# KM_BD01.net
KiCad netlist of a schematic drawn in Altium Designer
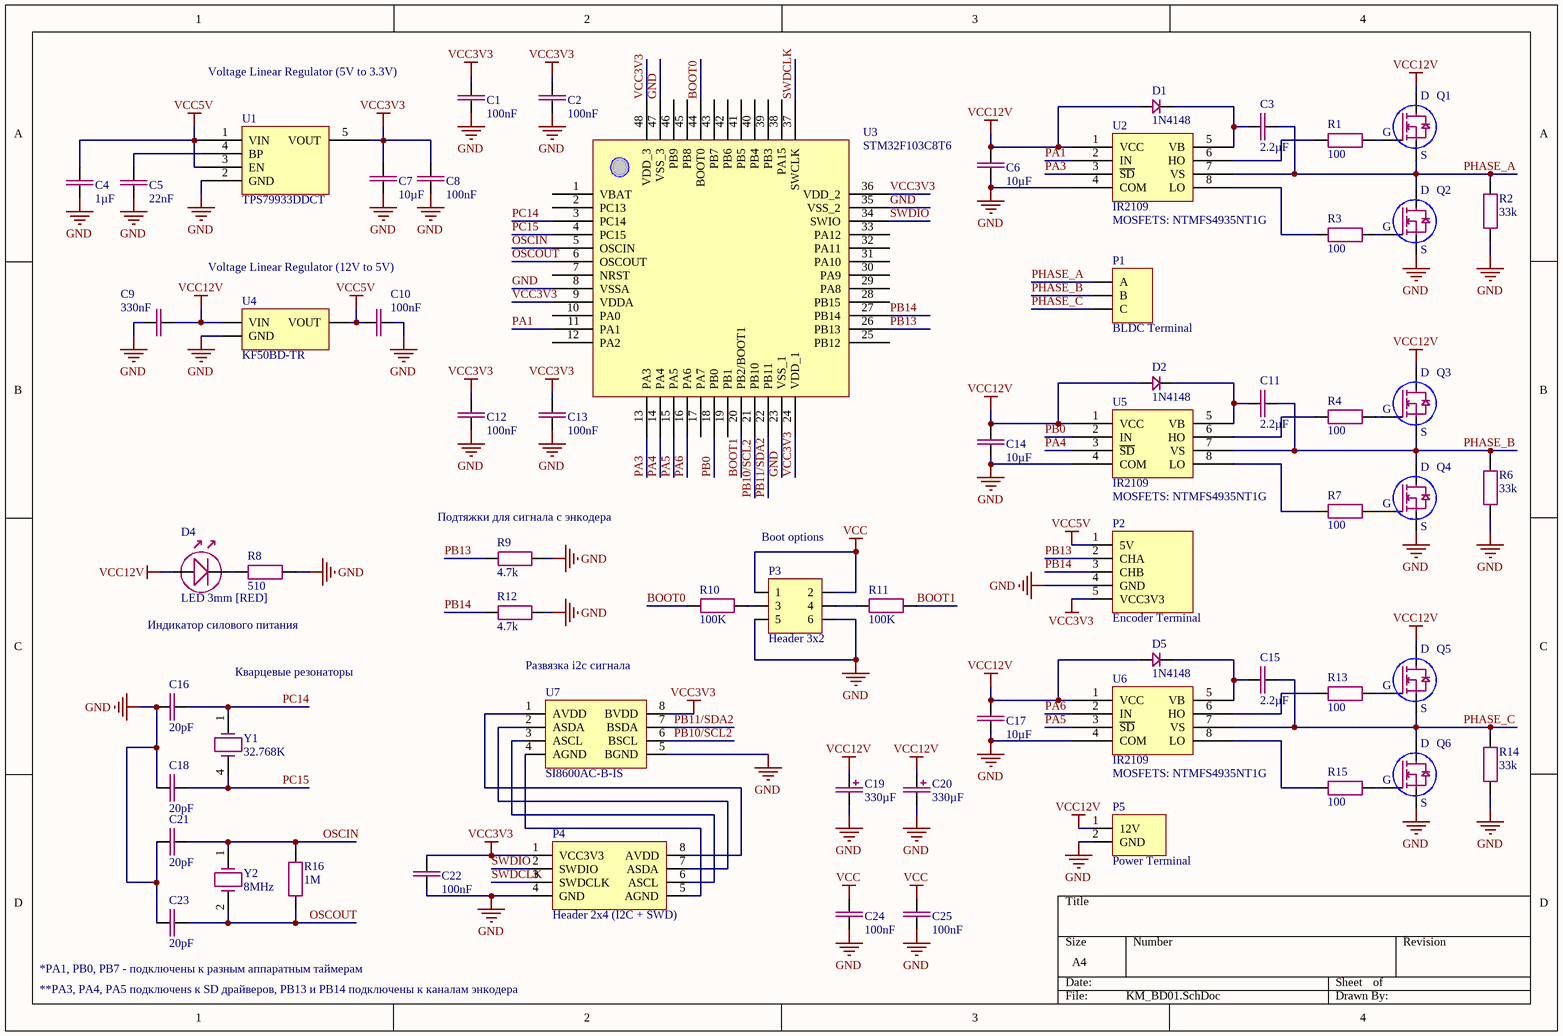
[diagram p0: KM_BD01.SchDoc]

(export (version "E")
  (design (tool "Eeschema 10.0.6"))
  (components
    (comp (ref "C1")
      (value "100nF")
      (footprint "KM_BD01:SMD 1206 CAP")
      (description "Capacitor 100nF [104]")
      (libsource (lib "KM_BD01") (part "100nF"))
    )
    (comp (ref "C2")
      (value "100nF")
      (footprint "KM_BD01:SMD 1206 CAP")
      (description "Capacitor 100nF [104]")
      (libsource (lib "KM_BD01") (part "100nF"))
    )
    (comp (ref "C3")
      (value "2.2µF")
      (footprint "KM_BD01:SMD 1206 CAP")
      (description "Capacitor 2.2µF [205]")
      (libsource (lib "KM_BD01") (part "2.2µF"))
    )
    (comp (ref "C4")
      (value "1µF")
      (footprint "KM_BD01:SMD 1206 CAP")
      (description "Capacitor 1µF [105]")
      (libsource (lib "KM_BD01") (part "1µF"))
    )
    (comp (ref "C5")
      (value "22nF")
      (footprint "KM_BD01:SMD 1206 CAP")
      (description "Capacitor 22nF [223]")
      (libsource (lib "KM_BD01") (part "22nF"))
    )
    (comp (ref "C6")
      (value "10µF")
      (footprint "KM_BD01:SMD 1206 CAP")
      (description "Capacitor 10µF [106]")
      (libsource (lib "KM_BD01") (part "10µF"))
    )
    (comp (ref "C7")
      (value "10µF")
      (footprint "KM_BD01:SMD 1206 CAP")
      (description "Capacitor 10µF [106]")
      (libsource (lib "KM_BD01") (part "10µF"))
    )
    (comp (ref "C8")
      (value "100nF")
      (footprint "KM_BD01:SMD 1206 CAP")
      (description "Capacitor 100nF [104]")
      (libsource (lib "KM_BD01") (part "100nF"))
    )
    (comp (ref "C9")
      (value "330nF")
      (footprint "KM_BD01:SMD 1206 CAP")
      (description "Capacitor 330nF [334]")
      (libsource (lib "KM_BD01") (part "330nF"))
    )
    (comp (ref "C10")
      (value "100nF")
      (footprint "KM_BD01:SMD 1206 CAP")
      (description "Capacitor 100nF [104]")
      (libsource (lib "KM_BD01") (part "100nF"))
    )
    (comp (ref "C11")
      (value "2.2µF")
      (footprint "KM_BD01:SMD 1206 CAP")
      (description "Capacitor 2.2µF [205]")
      (libsource (lib "KM_BD01") (part "2.2µF"))
    )
    (comp (ref "C12")
      (value "100nF")
      (footprint "KM_BD01:SMD 1206 CAP")
      (description "Capacitor 100nF [104]")
      (libsource (lib "KM_BD01") (part "100nF"))
    )
    (comp (ref "C13")
      (value "100nF")
      (footprint "KM_BD01:SMD 1206 CAP")
      (description "Capacitor 100nF [104]")
      (libsource (lib "KM_BD01") (part "100nF"))
    )
    (comp (ref "C14")
      (value "10µF")
      (footprint "KM_BD01:SMD 1206 CAP")
      (description "Capacitor 10µF [106]")
      (libsource (lib "KM_BD01") (part "10µF"))
    )
    (comp (ref "C15")
      (value "2.2µF")
      (footprint "KM_BD01:SMD 1206 CAP")
      (description "Capacitor 2.2µF [205]")
      (libsource (lib "KM_BD01") (part "2.2µF"))
    )
    (comp (ref "C16")
      (value "20pF")
      (footprint "KM_BD01:SMD 1206 CAP")
      (description "Capacitor 20pF")
      (libsource (lib "KM_BD01") (part "20pF"))
    )
    (comp (ref "C17")
      (value "10µF")
      (footprint "KM_BD01:SMD 1206 CAP")
      (description "Capacitor 10µF [106]")
      (libsource (lib "KM_BD01") (part "10µF"))
    )
    (comp (ref "C18")
      (value "20pF")
      (footprint "KM_BD01:SMD 1206 CAP")
      (description "Capacitor 20pF")
      (libsource (lib "KM_BD01") (part "20pF"))
    )
    (comp (ref "C19")
      (value "330µF")
      (footprint "KM_BD01:THD 6.3x11 CAP")
      (description "Capacitor 330µF [336]")
      (libsource (lib "KM_BD01") (part "330µF"))
    )
    (comp (ref "C20")
      (value "330µF")
      (footprint "KM_BD01:THD 6.3x11 CAP")
      (description "Capacitor 330µF [336]")
      (libsource (lib "KM_BD01") (part "330µF"))
    )
    (comp (ref "C21")
      (value "20pF")
      (footprint "KM_BD01:SMD 1206 CAP")
      (description "Capacitor 20pF")
      (libsource (lib "KM_BD01") (part "20pF"))
    )
    (comp (ref "C22")
      (value "100nF")
      (footprint "KM_BD01:SMD 1206 CAP")
      (description "Capacitor 100nF [104]")
      (libsource (lib "KM_BD01") (part "100nF"))
    )
    (comp (ref "C23")
      (value "20pF")
      (footprint "KM_BD01:SMD 1206 CAP")
      (description "Capacitor 20pF")
      (libsource (lib "KM_BD01") (part "20pF"))
    )
    (comp (ref "C24")
      (value "100nF")
      (footprint "KM_BD01:SMD 1206 CAP")
      (description "Capacitor 100nF [104]")
      (libsource (lib "KM_BD01") (part "100nF"))
    )
    (comp (ref "C25")
      (value "100nF")
      (footprint "KM_BD01:SMD 1206 CAP")
      (description "Capacitor 100nF [104]")
      (libsource (lib "KM_BD01") (part "100nF"))
    )
    (comp (ref "D1")
      (value "1N4148")
      (footprint "KM_BD01:DO-35")
      (description "Fast diode")
      (libsource (lib "KM_BD01") (part "1N4148"))
    )
    (comp (ref "D2")
      (value "1N4148")
      (footprint "KM_BD01:DO-35")
      (description "Fast diode")
      (libsource (lib "KM_BD01") (part "1N4148"))
    )
    (comp (ref "D4")
      (value "LED 3mm [RED]")
      (footprint "KM_BD01:LED 3mm RED")
      (libsource (lib "KM_BD01") (part "LED 3mm [RED]"))
    )
    (comp (ref "D5")
      (value "1N4148")
      (footprint "KM_BD01:DO-35")
      (description "Fast diode")
      (libsource (lib "KM_BD01") (part "1N4148"))
    )
    (comp (ref "P1")
      (value "BLDC Terminal")
      (footprint "KM_BD01:Universal 3-Phase Terminal")
      (description "3-pad terminal")
      (libsource (lib "KM_BD01") (part "BLDC Terminal"))
    )
    (comp (ref "P2")
      (value "Encoder Terminal")
      (footprint "KM_BD01:PLS_5")
      (description "5-pin PLS terminal")
      (libsource (lib "KM_BD01") (part "Encoder Terminal"))
    )
    (comp (ref "P3")
      (value "Header 3x2")
      (footprint "KM_BD01:PLS_3x2 (Without legs)")
      (description "6-pin PLS terminal")
      (libsource (lib "KM_BD01") (part "Header 3x2"))
    )
    (comp (ref "P4")
      (value "Header 2x4 (I2C + SWD)")
      (footprint "KM_BD01:PLS_4x2")
      (description "8-pin PLS terminal")
      (libsource (lib "KM_BD01") (part "Header 2x4 (I2C + SWD)"))
    )
    (comp (ref "P5")
      (value "Power Terminal")
      (footprint "KM_BD01:Universal Power Terminal")
      (description "12V 2-pad terminal")
      (libsource (lib "KM_BD01") (part "Power Terminal"))
    )
    (comp (ref "Q1")
      (value "NTMFS4935NT1G")
      (footprint "KM_BD01:SO-8FL")
      (description "Mosfet [OptiMOS]")
      (libsource (lib "KM_BD01") (part "NTMFS4935NT1G"))
    )
    (comp (ref "Q2")
      (value "NTMFS4935NT1G")
      (footprint "KM_BD01:SO-8FL")
      (description "Mosfet [OptiMOS]")
      (libsource (lib "KM_BD01") (part "NTMFS4935NT1G"))
    )
    (comp (ref "Q3")
      (value "NTMFS4935NT1G")
      (footprint "KM_BD01:SO-8FL")
      (description "Mosfet [OptiMOS]")
      (libsource (lib "KM_BD01") (part "NTMFS4935NT1G"))
    )
    (comp (ref "Q4")
      (value "NTMFS4935NT1G")
      (footprint "KM_BD01:SO-8FL")
      (description "Mosfet [OptiMOS]")
      (libsource (lib "KM_BD01") (part "NTMFS4935NT1G"))
    )
    (comp (ref "Q5")
      (value "NTMFS4935NT1G")
      (footprint "KM_BD01:SO-8FL")
      (description "Mosfet [OptiMOS]")
      (libsource (lib "KM_BD01") (part "NTMFS4935NT1G"))
    )
    (comp (ref "Q6")
      (value "NTMFS4935NT1G")
      (footprint "KM_BD01:SO-8FL")
      (description "Mosfet [OptiMOS]")
      (libsource (lib "KM_BD01") (part "NTMFS4935NT1G"))
    )
    (comp (ref "R1")
      (value "100")
      (footprint "KM_BD01:SMD 1206 RES")
      (description "Resistor")
      (libsource (lib "KM_BD01") (part "100"))
    )
    (comp (ref "R2")
      (value "33k")
      (footprint "KM_BD01:SMD 1206 RES")
      (description "Resistor")
      (libsource (lib "KM_BD01") (part "33k"))
    )
    (comp (ref "R3")
      (value "100")
      (footprint "KM_BD01:SMD 1206 RES")
      (description "Resistor")
      (libsource (lib "KM_BD01") (part "100"))
    )
    (comp (ref "R4")
      (value "100")
      (footprint "KM_BD01:SMD 1206 RES")
      (description "Resistor")
      (libsource (lib "KM_BD01") (part "100"))
    )
    (comp (ref "R6")
      (value "33k")
      (footprint "KM_BD01:SMD 1206 RES")
      (description "Resistor")
      (libsource (lib "KM_BD01") (part "33k"))
    )
    (comp (ref "R7")
      (value "100")
      (footprint "KM_BD01:SMD 1206 RES")
      (description "Resistor")
      (libsource (lib "KM_BD01") (part "100"))
    )
    (comp (ref "R8")
      (value "510")
      (footprint "KM_BD01:SMD 1206 RES")
      (description "Resistor")
      (libsource (lib "KM_BD01") (part "510"))
    )
    (comp (ref "R9")
      (value "4.7k")
      (footprint "KM_BD01:SMD 1206 RES")
      (description "Resistor")
      (libsource (lib "KM_BD01") (part "4.7k"))
    )
    (comp (ref "R10")
      (value "100K")
      (footprint "KM_BD01:SMD 1206 RES")
      (description "Resistor")
      (libsource (lib "KM_BD01") (part "100K"))
    )
    (comp (ref "R11")
      (value "100K")
      (footprint "KM_BD01:SMD 1206 RES")
      (description "Resistor")
      (libsource (lib "KM_BD01") (part "100K"))
    )
    (comp (ref "R12")
      (value "4.7k")
      (footprint "KM_BD01:SMD 1206 RES")
      (description "Resistor")
      (libsource (lib "KM_BD01") (part "4.7k"))
    )
    (comp (ref "R13")
      (value "100")
      (footprint "KM_BD01:SMD 1206 RES")
      (description "Resistor")
      (libsource (lib "KM_BD01") (part "100"))
    )
    (comp (ref "R14")
      (value "33k")
      (footprint "KM_BD01:SMD 1206 RES")
      (description "Resistor")
      (libsource (lib "KM_BD01") (part "33k"))
    )
    (comp (ref "R15")
      (value "100")
      (footprint "KM_BD01:SMD 1206 RES")
      (description "Resistor")
      (libsource (lib "KM_BD01") (part "100"))
    )
    (comp (ref "R16")
      (value "1M")
      (footprint "KM_BD01:SMD 1206 RES")
      (description "Resistor")
      (libsource (lib "KM_BD01") (part "1M"))
    )
    (comp (ref "U1")
      (value "TPS79933DDCT")
      (footprint "KM_BD01:SOT95P245X110-5N")
      (description "Linear Voltage Regulator (3.3V)")
      (libsource (lib "KM_BD01") (part "TPS79933DDCT"))
    )
    (comp (ref "U2")
      (value "IR2109")
      (footprint "KM_BD01:SOIC-8")
      (description "Fast Half-Bridge Driver")
      (libsource (lib "KM_BD01") (part "IR2109"))
    )
    (comp (ref "U3")
      (value "STM32F103C8T6")
      (footprint "KM_BD01:TQFP-48")
      (description "Microcontroller")
      (libsource (lib "KM_BD01") (part "STM32F103C8T6"))
    )
    (comp (ref "U4")
      (value "KF50BD-TR")
      (footprint "KM_BD01:SOIC-8 (KF50BD-TR)")
      (description "Linear Voltage Regulator (5V)")
      (libsource (lib "KM_BD01") (part "KF50BD-TR"))
    )
    (comp (ref "U5")
      (value "IR2109")
      (footprint "KM_BD01:SOIC-8")
      (description "Fast Half-Bridge Driver")
      (libsource (lib "KM_BD01") (part "IR2109"))
    )
    (comp (ref "U6")
      (value "IR2109")
      (footprint "KM_BD01:SOIC-8")
      (description "Fast Half-Bridge Driver")
      (libsource (lib "KM_BD01") (part "IR2109"))
    )
    (comp (ref "U7")
      (value "SI8600AC-B-IS")
      (footprint "KM_BD01:SOIC-8")
      (description "Bidirectional I2C isolator")
      (libsource (lib "KM_BD01") (part "SI8600AC-B-IS"))
    )
    (comp (ref "Y1")
      (value "32.768K")
      (footprint "KM_BD01:SMD 0803-8P4")
      (description "Oscillator")
      (libsource (lib "KM_BD01") (part "32.768K"))
    )
    (comp (ref "Y2")
      (value "8MHz")
      (footprint "KM_BD01:HC-49SM")
      (description "Oscillator")
      (libsource (lib "KM_BD01") (part "8MHz"))
    )
  )
  (nets
    (net (code "1") (name "/BOOT0") (class "Default")
      (node (ref "R10") (pin "1") (pinfunction "1_1") (pintype "passive"))
      (node (ref "U3") (pin "44") (pinfunction "BOOT0_44") (pintype "passive"))
    )
    (net (code "2") (name "/BOOT1") (class "Default")
      (node (ref "R11") (pin "2") (pinfunction "2_2") (pintype "passive"))
      (node (ref "U3") (pin "20") (pinfunction "PB2/BOOT1_20") (pintype "passive"))
    )
    (net (code "3") (name "/OSCIN") (class "Default")
      (node (ref "C21") (pin "2") (pinfunction "2_2") (pintype "passive"))
      (node (ref "R16") (pin "2") (pinfunction "2_2") (pintype "passive"))
      (node (ref "U3") (pin "5") (pinfunction "OSCIN_5") (pintype "passive"))
      (node (ref "Y2") (pin "1") (pinfunction "1_1") (pintype "passive"))
    )
    (net (code "4") (name "/OSCOUT") (class "Default")
      (node (ref "C23") (pin "2") (pinfunction "2_2") (pintype "passive"))
      (node (ref "R16") (pin "1") (pinfunction "1_1") (pintype "passive"))
      (node (ref "U3") (pin "6") (pinfunction "OSCOUT_6") (pintype "passive"))
      (node (ref "Y2") (pin "2") (pinfunction "2_2") (pintype "passive"))
    )
    (net (code "5") (name "/PA1") (class "Default")
      (node (ref "U2") (pin "2") (pinfunction "IN_2") (pintype "passive"))
      (node (ref "U3") (pin "11") (pinfunction "PA1_11") (pintype "passive"))
    )
    (net (code "6") (name "/PA3") (class "Default")
      (node (ref "U2") (pin "3") (pinfunction "~{SD}_3") (pintype "passive"))
      (node (ref "U3") (pin "13") (pinfunction "PA3_13") (pintype "passive"))
    )
    (net (code "7") (name "/PA4") (class "Default")
      (node (ref "U3") (pin "14") (pinfunction "PA4_14") (pintype "passive"))
      (node (ref "U5") (pin "3") (pinfunction "~{SD}_3") (pintype "passive"))
    )
    (net (code "8") (name "/PA5") (class "Default")
      (node (ref "U3") (pin "15") (pinfunction "PA5_15") (pintype "passive"))
      (node (ref "U6") (pin "3") (pinfunction "~{SD}_3") (pintype "passive"))
    )
    (net (code "9") (name "/PA6") (class "Default")
      (node (ref "U3") (pin "16") (pinfunction "PA6_16") (pintype "passive"))
      (node (ref "U6") (pin "2") (pinfunction "IN_2") (pintype "passive"))
    )
    (net (code "10") (name "/PB0") (class "Default")
      (node (ref "U3") (pin "18") (pinfunction "PB0_18") (pintype "passive"))
      (node (ref "U5") (pin "2") (pinfunction "IN_2") (pintype "passive"))
    )
    (net (code "11") (name "/PB10{slash}SCL2") (class "Default")
      (node (ref "U3") (pin "21") (pinfunction "PB10_21") (pintype "passive"))
      (node (ref "U7") (pin "6") (pinfunction "BSCL_6") (pintype "passive"))
    )
    (net (code "12") (name "/PB11{slash}SDA2") (class "Default")
      (node (ref "U3") (pin "22") (pinfunction "PB11_22") (pintype "passive"))
      (node (ref "U7") (pin "7") (pinfunction "BSDA_7") (pintype "passive"))
    )
    (net (code "13") (name "/PB13") (class "Default")
      (node (ref "P2") (pin "2") (pinfunction "CHA_2") (pintype "passive"))
      (node (ref "R9") (pin "2") (pinfunction "2_2") (pintype "passive"))
      (node (ref "U3") (pin "26") (pinfunction "PB13_26") (pintype "passive"))
    )
    (net (code "14") (name "/PB14") (class "Default")
      (node (ref "P2") (pin "3") (pinfunction "CHB_3") (pintype "passive"))
      (node (ref "R12") (pin "2") (pinfunction "2_2") (pintype "passive"))
      (node (ref "U3") (pin "27") (pinfunction "PB14_27") (pintype "passive"))
    )
    (net (code "15") (name "/PC14") (class "Default")
      (node (ref "C16") (pin "2") (pinfunction "2_2") (pintype "passive"))
      (node (ref "U3") (pin "3") (pinfunction "PC14_3") (pintype "passive"))
      (node (ref "Y1") (pin "1") (pinfunction "1_1") (pintype "passive"))
    )
    (net (code "16") (name "/PC15") (class "Default")
      (node (ref "C18") (pin "2") (pinfunction "2_2") (pintype "passive"))
      (node (ref "U3") (pin "4") (pinfunction "PC15_4") (pintype "passive"))
      (node (ref "Y1") (pin "4") (pinfunction "4_4") (pintype "passive"))
    )
    (net (code "17") (name "/PHASE_A") (class "Default")
      (node (ref "C3") (pin "2") (pinfunction "2_2") (pintype "passive"))
      (node (ref "P1") (pin "1") (pinfunction "A_1") (pintype "passive"))
      (node (ref "Q1") (pin "2") (pinfunction "S_2") (pintype "passive"))
      (node (ref "Q2") (pin "3") (pinfunction "D_3") (pintype "passive"))
      (node (ref "R2") (pin "2") (pinfunction "2_2") (pintype "passive"))
      (node (ref "U2") (pin "7") (pinfunction "VS_7") (pintype "passive"))
    )
    (net (code "18") (name "/PHASE_B") (class "Default")
      (node (ref "C11") (pin "2") (pinfunction "2_2") (pintype "passive"))
      (node (ref "P1") (pin "2") (pinfunction "B_2") (pintype "passive"))
      (node (ref "Q3") (pin "2") (pinfunction "S_2") (pintype "passive"))
      (node (ref "Q4") (pin "3") (pinfunction "D_3") (pintype "passive"))
      (node (ref "R6") (pin "2") (pinfunction "2_2") (pintype "passive"))
      (node (ref "U5") (pin "7") (pinfunction "VS_7") (pintype "passive"))
    )
    (net (code "19") (name "/PHASE_C") (class "Default")
      (node (ref "C15") (pin "2") (pinfunction "2_2") (pintype "passive"))
      (node (ref "P1") (pin "3") (pinfunction "C_3") (pintype "passive"))
      (node (ref "Q5") (pin "2") (pinfunction "S_2") (pintype "passive"))
      (node (ref "Q6") (pin "3") (pinfunction "D_3") (pintype "passive"))
      (node (ref "R14") (pin "2") (pinfunction "2_2") (pintype "passive"))
      (node (ref "U6") (pin "7") (pinfunction "VS_7") (pintype "passive"))
    )
    (net (code "20") (name "/SWDCLK") (class "Default")
      (node (ref "P4") (pin "3") (pinfunction "SWDCLK_3") (pintype "passive"))
      (node (ref "U3") (pin "37") (pinfunction "SWCLK_37") (pintype "passive"))
    )
    (net (code "21") (name "/SWDIO") (class "Default")
      (node (ref "P4") (pin "2") (pinfunction "SWDIO_2") (pintype "passive"))
      (node (ref "U3") (pin "34") (pinfunction "SWIO_34") (pintype "passive"))
    )
    (net (code "22") (name "GND") (class "Default")
      (node (ref "C1") (pin "1") (pinfunction "1_1") (pintype "passive"))
      (node (ref "C10") (pin "2") (pinfunction "2_2") (pintype "passive"))
      (node (ref "C12") (pin "1") (pinfunction "1_1") (pintype "passive"))
      (node (ref "C13") (pin "1") (pinfunction "1_1") (pintype "passive"))
      (node (ref "C14") (pin "1") (pinfunction "1_1") (pintype "passive"))
      (node (ref "C16") (pin "1") (pinfunction "1_1") (pintype "passive"))
      (node (ref "C17") (pin "1") (pinfunction "1_1") (pintype "passive"))
      (node (ref "C18") (pin "1") (pinfunction "1_1") (pintype "passive"))
      (node (ref "C19") (pin "2") (pinfunction "2_2") (pintype "passive"))
      (node (ref "C2") (pin "1") (pinfunction "1_1") (pintype "passive"))
      (node (ref "C20") (pin "2") (pinfunction "2_2") (pintype "passive"))
      (node (ref "C21") (pin "1") (pinfunction "1_1") (pintype "passive"))
      (node (ref "C22") (pin "1") (pinfunction "1_1") (pintype "passive"))
      (node (ref "C23") (pin "1") (pinfunction "1_1") (pintype "passive"))
      (node (ref "C24") (pin "1") (pinfunction "1_1") (pintype "passive"))
      (node (ref "C25") (pin "1") (pinfunction "1_1") (pintype "passive"))
      (node (ref "C4") (pin "1") (pinfunction "1_1") (pintype "passive"))
      (node (ref "C5") (pin "1") (pinfunction "1_1") (pintype "passive"))
      (node (ref "C6") (pin "1") (pinfunction "1_1") (pintype "passive"))
      (node (ref "C7") (pin "1") (pinfunction "1_1") (pintype "passive"))
      (node (ref "C8") (pin "1") (pinfunction "1_1") (pintype "passive"))
      (node (ref "C9") (pin "1") (pinfunction "1_1") (pintype "passive"))
      (node (ref "P2") (pin "4") (pinfunction "GND_4") (pintype "passive"))
      (node (ref "P3") (pin "5") (pinfunction "5_5") (pintype "passive"))
      (node (ref "P3") (pin "6") (pinfunction "6_6") (pintype "passive"))
      (node (ref "P4") (pin "4") (pinfunction "GND_4") (pintype "passive"))
      (node (ref "P5") (pin "2") (pinfunction "GND_2") (pintype "passive"))
      (node (ref "Q2") (pin "2") (pinfunction "S_2") (pintype "passive"))
      (node (ref "Q4") (pin "2") (pinfunction "S_2") (pintype "passive"))
      (node (ref "Q6") (pin "2") (pinfunction "S_2") (pintype "passive"))
      (node (ref "R12") (pin "1") (pinfunction "1_1") (pintype "passive"))
      (node (ref "R14") (pin "1") (pinfunction "1_1") (pintype "passive"))
      (node (ref "R2") (pin "1") (pinfunction "1_1") (pintype "passive"))
      (node (ref "R6") (pin "1") (pinfunction "1_1") (pintype "passive"))
      (node (ref "R8") (pin "2") (pinfunction "2_2") (pintype "passive"))
      (node (ref "R9") (pin "1") (pinfunction "1_1") (pintype "passive"))
      (node (ref "U1") (pin "2") (pinfunction "GND_2") (pintype "passive"))
      (node (ref "U2") (pin "4") (pinfunction "COM_4") (pintype "passive"))
      (node (ref "U3") (pin "23") (pinfunction "VSS_1_23") (pintype "passive"))
      (node (ref "U3") (pin "35") (pinfunction "VSS_2_35") (pintype "passive"))
      (node (ref "U3") (pin "47") (pinfunction "VSS_3_47") (pintype "passive"))
      (node (ref "U3") (pin "8") (pinfunction "VSSA_8") (pintype "passive"))
      (node (ref "U4") (pin "2") (pinfunction "GND_2") (pintype "passive"))
      (node (ref "U5") (pin "4") (pinfunction "COM_4") (pintype "passive"))
      (node (ref "U6") (pin "4") (pinfunction "COM_4") (pintype "passive"))
      (node (ref "U7") (pin "5") (pinfunction "BGND_5") (pintype "passive"))
    )
    (net (code "23") (name "Net-(D4-Pad2)") (class "Default")
      (node (ref "D4") (pin "2") (pinfunction "2_2") (pintype "passive"))
      (node (ref "R8") (pin "1") (pinfunction "1_1") (pintype "passive"))
    )
    (net (code "24") (name "Net-(P3-Pad3)") (class "Default")
      (node (ref "P3") (pin "3") (pinfunction "3_3") (pintype "passive"))
      (node (ref "R10") (pin "2") (pinfunction "2_2") (pintype "passive"))
    )
    (net (code "25") (name "Net-(P3-Pad4)") (class "Default")
      (node (ref "P3") (pin "4") (pinfunction "4_4") (pintype "passive"))
      (node (ref "R11") (pin "1") (pinfunction "1_1") (pintype "passive"))
    )
    (net (code "26") (name "Net-(P4-AGND)") (class "Default")
      (node (ref "P4") (pin "5") (pinfunction "AGND_5") (pintype "passive"))
      (node (ref "U7") (pin "4") (pinfunction "AGND_4") (pintype "passive"))
    )
    (net (code "27") (name "Net-(P4-ASCL)") (class "Default")
      (node (ref "P4") (pin "6") (pinfunction "ASCL_6") (pintype "passive"))
      (node (ref "U7") (pin "3") (pinfunction "ASCL_3") (pintype "passive"))
    )
    (net (code "28") (name "Net-(P4-ASDA)") (class "Default")
      (node (ref "P4") (pin "7") (pinfunction "ASDA_7") (pintype "passive"))
      (node (ref "U7") (pin "2") (pinfunction "ASDA_2") (pintype "passive"))
    )
    (net (code "29") (name "Net-(P4-AVDD)") (class "Default")
      (node (ref "P4") (pin "8") (pinfunction "AVDD_8") (pintype "passive"))
      (node (ref "U7") (pin "1") (pinfunction "AVDD_1") (pintype "passive"))
    )
    (net (code "30") (name "Net-(Q1-G)") (class "Default")
      (node (ref "Q1") (pin "1") (pinfunction "G_1") (pintype "passive"))
      (node (ref "R1") (pin "2") (pinfunction "2_2") (pintype "passive"))
    )
    (net (code "31") (name "Net-(Q2-G)") (class "Default")
      (node (ref "Q2") (pin "1") (pinfunction "G_1") (pintype "passive"))
      (node (ref "R3") (pin "2") (pinfunction "2_2") (pintype "passive"))
    )
    (net (code "32") (name "Net-(Q3-G)") (class "Default")
      (node (ref "Q3") (pin "1") (pinfunction "G_1") (pintype "passive"))
      (node (ref "R4") (pin "2") (pinfunction "2_2") (pintype "passive"))
    )
    (net (code "33") (name "Net-(Q4-G)") (class "Default")
      (node (ref "Q4") (pin "1") (pinfunction "G_1") (pintype "passive"))
      (node (ref "R7") (pin "2") (pinfunction "2_2") (pintype "passive"))
    )
    (net (code "34") (name "Net-(Q5-G)") (class "Default")
      (node (ref "Q5") (pin "1") (pinfunction "G_1") (pintype "passive"))
      (node (ref "R13") (pin "2") (pinfunction "2_2") (pintype "passive"))
    )
    (net (code "35") (name "Net-(Q6-G)") (class "Default")
      (node (ref "Q6") (pin "1") (pinfunction "G_1") (pintype "passive"))
      (node (ref "R15") (pin "2") (pinfunction "2_2") (pintype "passive"))
    )
    (net (code "36") (name "Net-(U1-BP)") (class "Default")
      (node (ref "C5") (pin "2") (pinfunction "2_2") (pintype "passive"))
      (node (ref "U1") (pin "4") (pinfunction "BP_4") (pintype "passive"))
    )
    (net (code "37") (name "Net-(U2-HO)") (class "Default")
      (node (ref "R1") (pin "1") (pinfunction "1_1") (pintype "passive"))
      (node (ref "U2") (pin "6") (pinfunction "HO_6") (pintype "passive"))
    )
    (net (code "38") (name "Net-(U2-LO)") (class "Default")
      (node (ref "R3") (pin "1") (pinfunction "1_1") (pintype "passive"))
      (node (ref "U2") (pin "8") (pinfunction "LO_8") (pintype "passive"))
    )
    (net (code "39") (name "Net-(U2-VB)") (class "Default")
      (node (ref "C3") (pin "1") (pinfunction "1_1") (pintype "passive"))
      (node (ref "D1") (pin "2") (pinfunction "2_2") (pintype "passive"))
      (node (ref "U2") (pin "5") (pinfunction "VB_5") (pintype "passive"))
    )
    (net (code "40") (name "Net-(U5-HO)") (class "Default")
      (node (ref "R4") (pin "1") (pinfunction "1_1") (pintype "passive"))
      (node (ref "U5") (pin "6") (pinfunction "HO_6") (pintype "passive"))
    )
    (net (code "41") (name "Net-(U5-LO)") (class "Default")
      (node (ref "R7") (pin "1") (pinfunction "1_1") (pintype "passive"))
      (node (ref "U5") (pin "8") (pinfunction "LO_8") (pintype "passive"))
    )
    (net (code "42") (name "Net-(U5-VB)") (class "Default")
      (node (ref "C11") (pin "1") (pinfunction "1_1") (pintype "passive"))
      (node (ref "D2") (pin "2") (pinfunction "2_2") (pintype "passive"))
      (node (ref "U5") (pin "5") (pinfunction "VB_5") (pintype "passive"))
    )
    (net (code "43") (name "Net-(U6-HO)") (class "Default")
      (node (ref "R13") (pin "1") (pinfunction "1_1") (pintype "passive"))
      (node (ref "U6") (pin "6") (pinfunction "HO_6") (pintype "passive"))
    )
    (net (code "44") (name "Net-(U6-LO)") (class "Default")
      (node (ref "R15") (pin "1") (pinfunction "1_1") (pintype "passive"))
      (node (ref "U6") (pin "8") (pinfunction "LO_8") (pintype "passive"))
    )
    (net (code "45") (name "Net-(U6-VB)") (class "Default")
      (node (ref "C15") (pin "1") (pinfunction "1_1") (pintype "passive"))
      (node (ref "D5") (pin "2") (pinfunction "2_2") (pintype "passive"))
      (node (ref "U6") (pin "5") (pinfunction "VB_5") (pintype "passive"))
    )
    (net (code "46") (name "VCC") (class "Default")
      (node (ref "C24") (pin "2") (pinfunction "2_2") (pintype "passive"))
      (node (ref "C25") (pin "2") (pinfunction "2_2") (pintype "passive"))
      (node (ref "P3") (pin "1") (pinfunction "1_1") (pintype "passive"))
      (node (ref "P3") (pin "2") (pinfunction "2_2") (pintype "passive"))
    )
    (net (code "47") (name "VCC3V3") (class "Default")
      (node (ref "C1") (pin "2") (pinfunction "2_2") (pintype "passive"))
      (node (ref "C12") (pin "2") (pinfunction "2_2") (pintype "passive"))
      (node (ref "C13") (pin "2") (pinfunction "2_2") (pintype "passive"))
      (node (ref "C2") (pin "2") (pinfunction "2_2") (pintype "passive"))
      (node (ref "C22") (pin "2") (pinfunction "2_2") (pintype "passive"))
      (node (ref "C7") (pin "2") (pinfunction "2_2") (pintype "passive"))
      (node (ref "C8") (pin "2") (pinfunction "2_2") (pintype "passive"))
      (node (ref "P2") (pin "5") (pinfunction "VCC3V3_5") (pintype "passive"))
      (node (ref "P4") (pin "1") (pinfunction "VCC3V3_1") (pintype "passive"))
      (node (ref "U1") (pin "5") (pinfunction "VOUT_5") (pintype "passive"))
      (node (ref "U3") (pin "24") (pinfunction "VDD_1_24") (pintype "passive"))
      (node (ref "U3") (pin "36") (pinfunction "VDD_2_36") (pintype "passive"))
      (node (ref "U3") (pin "48") (pinfunction "VDD_3_48") (pintype "passive"))
      (node (ref "U3") (pin "9") (pinfunction "VDDA_9") (pintype "passive"))
      (node (ref "U7") (pin "8") (pinfunction "BVDD_8") (pintype "passive"))
    )
    (net (code "48") (name "VCC5V") (class "Default")
      (node (ref "C10") (pin "1") (pinfunction "1_1") (pintype "passive"))
      (node (ref "C4") (pin "2") (pinfunction "2_2") (pintype "passive"))
      (node (ref "P2") (pin "1") (pinfunction "5V_1") (pintype "passive"))
      (node (ref "U1") (pin "1") (pinfunction "VIN_1") (pintype "passive"))
      (node (ref "U1") (pin "3") (pinfunction "EN_3") (pintype "passive"))
      (node (ref "U4") (pin "1") (pinfunction "VOUT_1") (pintype "passive"))
    )
    (net (code "49") (name "VCC12V") (class "Default")
      (node (ref "C14") (pin "2") (pinfunction "2_2") (pintype "passive"))
      (node (ref "C17") (pin "2") (pinfunction "2_2") (pintype "passive"))
      (node (ref "C19") (pin "1") (pinfunction "1_1") (pintype "passive"))
      (node (ref "C20") (pin "1") (pinfunction "1_1") (pintype "passive"))
      (node (ref "C6") (pin "2") (pinfunction "2_2") (pintype "passive"))
      (node (ref "C9") (pin "2") (pinfunction "2_2") (pintype "passive"))
      (node (ref "D1") (pin "1") (pinfunction "1_1") (pintype "passive"))
      (node (ref "D2") (pin "1") (pinfunction "1_1") (pintype "passive"))
      (node (ref "D4") (pin "1") (pinfunction "1_1") (pintype "passive"))
      (node (ref "D5") (pin "1") (pinfunction "1_1") (pintype "passive"))
      (node (ref "P5") (pin "1") (pinfunction "12V_1") (pintype "passive"))
      (node (ref "Q1") (pin "3") (pinfunction "D_3") (pintype "passive"))
      (node (ref "Q3") (pin "3") (pinfunction "D_3") (pintype "passive"))
      (node (ref "Q5") (pin "3") (pinfunction "D_3") (pintype "passive"))
      (node (ref "U2") (pin "1") (pinfunction "VCC_1") (pintype "passive"))
      (node (ref "U4") (pin "5") (pinfunction "VIN_5") (pintype "passive"))
      (node (ref "U5") (pin "1") (pinfunction "VCC_1") (pintype "passive"))
      (node (ref "U6") (pin "1") (pinfunction "VCC_1") (pintype "passive"))
    )
    (net (code "50") (name "unconnected-(U3-NRST-Pad7)") (class "Default")
      (node (ref "U3") (pin "7") (pinfunction "NRST_7") (pintype "passive"))
    )
    (net (code "51") (name "unconnected-(U3-PA0-Pad10)") (class "Default")
      (node (ref "U3") (pin "10") (pinfunction "PA0_10") (pintype "passive"))
    )
    (net (code "52") (name "unconnected-(U3-PA2-Pad12)") (class "Default")
      (node (ref "U3") (pin "12") (pinfunction "PA2_12") (pintype "passive"))
    )
    (net (code "53") (name "unconnected-(U3-PA7-Pad17)") (class "Default")
      (node (ref "U3") (pin "17") (pinfunction "PA7_17") (pintype "passive"))
    )
    (net (code "54") (name "unconnected-(U3-PA8-Pad29)") (class "Default")
      (node (ref "U3") (pin "29") (pinfunction "PA8_29") (pintype "passive"))
    )
    (net (code "55") (name "unconnected-(U3-PA9-Pad30)") (class "Default")
      (node (ref "U3") (pin "30") (pinfunction "PA9_30") (pintype "passive"))
    )
    (net (code "56") (name "unconnected-(U3-PA10-Pad31)") (class "Default")
      (node (ref "U3") (pin "31") (pinfunction "PA10_31") (pintype "passive"))
    )
    (net (code "57") (name "unconnected-(U3-PA11-Pad32)") (class "Default")
      (node (ref "U3") (pin "32") (pinfunction "PA11_32") (pintype "passive"))
    )
    (net (code "58") (name "unconnected-(U3-PA12-Pad33)") (class "Default")
      (node (ref "U3") (pin "33") (pinfunction "PA12_33") (pintype "passive"))
    )
    (net (code "59") (name "unconnected-(U3-PA15-Pad38)") (class "Default")
      (node (ref "U3") (pin "38") (pinfunction "PA15_38") (pintype "passive"))
    )
    (net (code "60") (name "unconnected-(U3-PB1-Pad19)") (class "Default")
      (node (ref "U3") (pin "19") (pinfunction "PB1_19") (pintype "passive"))
    )
    (net (code "61") (name "unconnected-(U3-PB3-Pad39)") (class "Default")
      (node (ref "U3") (pin "39") (pinfunction "PB3_39") (pintype "passive"))
    )
    (net (code "62") (name "unconnected-(U3-PB4-Pad40)") (class "Default")
      (node (ref "U3") (pin "40") (pinfunction "PB4_40") (pintype "passive"))
    )
    (net (code "63") (name "unconnected-(U3-PB5-Pad41)") (class "Default")
      (node (ref "U3") (pin "41") (pinfunction "PB5_41") (pintype "passive"))
    )
    (net (code "64") (name "unconnected-(U3-PB6-Pad42)") (class "Default")
      (node (ref "U3") (pin "42") (pinfunction "PB6_42") (pintype "passive"))
    )
    (net (code "65") (name "unconnected-(U3-PB7-Pad43)") (class "Default")
      (node (ref "U3") (pin "43") (pinfunction "PB7_43") (pintype "passive"))
    )
    (net (code "66") (name "unconnected-(U3-PB8-Pad45)") (class "Default")
      (node (ref "U3") (pin "45") (pinfunction "PB8_45") (pintype "passive"))
    )
    (net (code "67") (name "unconnected-(U3-PB9-Pad46)") (class "Default")
      (node (ref "U3") (pin "46") (pinfunction "PB9_46") (pintype "passive"))
    )
    (net (code "68") (name "unconnected-(U3-PB12-Pad25)") (class "Default")
      (node (ref "U3") (pin "25") (pinfunction "PB12_25") (pintype "passive"))
    )
    (net (code "69") (name "unconnected-(U3-PB15-Pad28)") (class "Default")
      (node (ref "U3") (pin "28") (pinfunction "PB15_28") (pintype "passive"))
    )
    (net (code "70") (name "unconnected-(U3-PC13-Pad2)") (class "Default")
      (node (ref "U3") (pin "2") (pinfunction "PC13_2") (pintype "passive"))
    )
    (net (code "71") (name "unconnected-(U3-VBAT-Pad1)") (class "Default")
      (node (ref "U3") (pin "1") (pinfunction "VBAT_1") (pintype "passive"))
    )
  )
)
